# limiter.net
KiCad netlist of a schematic drawn in EAGLE
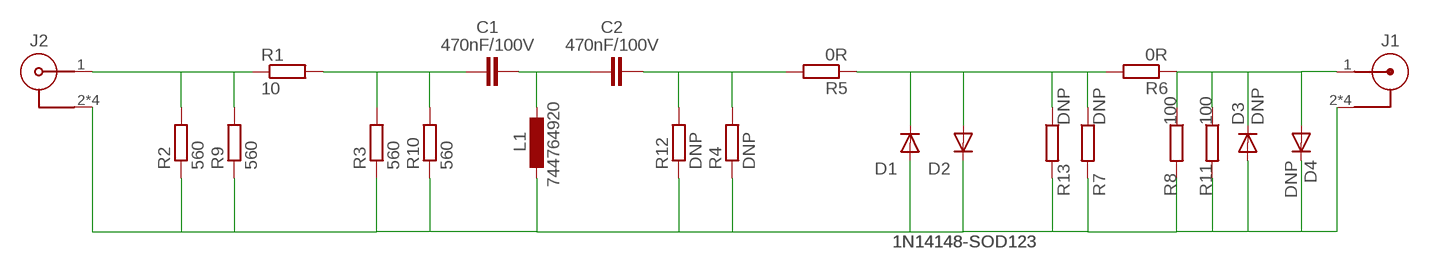
[diagram p0: schematic, sheet 1]

(export (version "E")
  (design (tool "Eeschema 10.0.6"))
  (components
    (comp (ref "C1")
      (value "470nF/100V")
      (footprint "eagle-import:C0805K")
      (libsource (lib "eagle-import") (part "C-EUC0805K"))
    )
    (comp (ref "C2")
      (value "470nF/100V")
      (footprint "eagle-import:C0805K")
      (libsource (lib "eagle-import") (part "C-EUC0805K"))
    )
    (comp (ref "D1")
      (value "1N14148-SOD123")
      (footprint "eagle-import:SOD123")
      (libsource (lib "eagle-import") (part "DIODE-SOD123"))
    )
    (comp (ref "D2")
      (value "1N14148-SOD123")
      (footprint "eagle-import:SOD123")
      (libsource (lib "eagle-import") (part "DIODE-SOD123"))
    )
    (comp (ref "D3")
      (value "DNP")
      (footprint "eagle-import:SOD123")
      (libsource (lib "eagle-import") (part "DIODE-SOD123"))
    )
    (comp (ref "D4")
      (value "DNP")
      (footprint "eagle-import:SOD123")
      (libsource (lib "eagle-import") (part "DIODE-SOD123"))
    )
    (comp (ref "J1")
      (value "60314202124525")
      (footprint "eagle-import:60314202124525")
      (libsource (lib "eagle-import") (part "60314202124525"))
    )
    (comp (ref "J2")
      (value "60312202114509")
      (footprint "eagle-import:60312202114509")
      (libsource (lib "eagle-import") (part "60312202114509"))
    )
    (comp (ref "L1")
      (value "744764920")
      (footprint "eagle-import:L3225M")
      (libsource (lib "eagle-import") (part "L-EUL3225M"))
    )
    (comp (ref "R1")
      (value "10")
      (footprint "eagle-import:R0805")
      (libsource (lib "eagle-import") (part "R-EU_R0805"))
    )
    (comp (ref "R2")
      (value "560")
      (footprint "eagle-import:R0805")
      (libsource (lib "eagle-import") (part "R-EU_R0805"))
    )
    (comp (ref "R3")
      (value "560")
      (footprint "eagle-import:R0805")
      (libsource (lib "eagle-import") (part "R-EU_R0805"))
    )
    (comp (ref "R4")
      (value "DNP")
      (footprint "eagle-import:R0805")
      (libsource (lib "eagle-import") (part "R-EU_R0805"))
    )
    (comp (ref "R5")
      (value "0R")
      (footprint "eagle-import:R0805")
      (libsource (lib "eagle-import") (part "R-EU_R0805"))
    )
    (comp (ref "R6")
      (value "0R")
      (footprint "eagle-import:R0805")
      (libsource (lib "eagle-import") (part "R-EU_R0805"))
    )
    (comp (ref "R7")
      (value "DNP")
      (footprint "eagle-import:R0805")
      (libsource (lib "eagle-import") (part "R-EU_R0805"))
    )
    (comp (ref "R8")
      (value "100")
      (footprint "eagle-import:R0805")
      (libsource (lib "eagle-import") (part "R-EU_R0805"))
    )
    (comp (ref "R9")
      (value "560")
      (footprint "eagle-import:R0805")
      (libsource (lib "eagle-import") (part "R-EU_R0805"))
    )
    (comp (ref "R10")
      (value "560")
      (footprint "eagle-import:R0805")
      (libsource (lib "eagle-import") (part "R-EU_R0805"))
    )
    (comp (ref "R11")
      (value "100")
      (footprint "eagle-import:R0805")
      (libsource (lib "eagle-import") (part "R-EU_R0805"))
    )
    (comp (ref "R12")
      (value "DNP")
      (footprint "eagle-import:R0805")
      (libsource (lib "eagle-import") (part "R-EU_R0805"))
    )
    (comp (ref "R13")
      (value "DNP")
      (footprint "eagle-import:R0805")
      (libsource (lib "eagle-import") (part "R-EU_R0805"))
    )
  )
  (nets
    (net (code "1") (name "Net-(C1-Pad1)") (class "Default")
      (node (ref "C1") (pin "1") (pinfunction "1_1") (pintype "passive"))
      (node (ref "R1") (pin "2") (pinfunction "2_2") (pintype "passive"))
      (node (ref "R10") (pin "2") (pinfunction "2_2") (pintype "passive"))
      (node (ref "R3") (pin "2") (pinfunction "2_2") (pintype "passive"))
    )
    (net (code "2") (name "Net-(C1-Pad2)") (class "Default")
      (node (ref "C1") (pin "2") (pinfunction "2_2") (pintype "passive"))
      (node (ref "C2") (pin "1") (pinfunction "1_1") (pintype "passive"))
      (node (ref "L1") (pin "1") (pinfunction "1_1") (pintype "passive"))
    )
    (net (code "3") (name "Net-(C2-Pad2)") (class "Default")
      (node (ref "C2") (pin "2") (pinfunction "2_2") (pintype "passive"))
      (node (ref "R12") (pin "2") (pinfunction "2_2") (pintype "passive"))
      (node (ref "R4") (pin "2") (pinfunction "2_2") (pintype "passive"))
      (node (ref "R5") (pin "2") (pinfunction "2_2") (pintype "passive"))
    )
    (net (code "4") (name "Net-(D1-PadA)") (class "Default")
      (node (ref "D1") (pin "A") (pinfunction "A_A") (pintype "passive"))
      (node (ref "D2") (pin "C") (pinfunction "C_C") (pintype "passive"))
      (node (ref "D3") (pin "A") (pinfunction "A_A") (pintype "passive"))
      (node (ref "D4") (pin "C") (pinfunction "C_C") (pintype "passive"))
      (node (ref "J1") (pin "2") (pinfunction "2_2") (pintype "passive"))
      (node (ref "J1") (pin "3") (pinfunction "2_3") (pintype "passive"))
      (node (ref "J1") (pin "4") (pinfunction "2_4") (pintype "passive"))
      (node (ref "J1") (pin "5") (pinfunction "2_5") (pintype "passive"))
      (node (ref "J2") (pin "2") (pinfunction "2_2") (pintype "passive"))
      (node (ref "J2") (pin "3") (pinfunction "2_3") (pintype "passive"))
      (node (ref "J2") (pin "4") (pinfunction "2_4") (pintype "passive"))
      (node (ref "J2") (pin "5") (pinfunction "2_5") (pintype "passive"))
      (node (ref "L1") (pin "2") (pinfunction "2_2") (pintype "passive"))
      (node (ref "R10") (pin "1") (pinfunction "1_1") (pintype "passive"))
      (node (ref "R11") (pin "2") (pinfunction "2_2") (pintype "passive"))
      (node (ref "R12") (pin "1") (pinfunction "1_1") (pintype "passive"))
      (node (ref "R13") (pin "2") (pinfunction "2_2") (pintype "passive"))
      (node (ref "R2") (pin "1") (pinfunction "1_1") (pintype "passive"))
      (node (ref "R3") (pin "1") (pinfunction "1_1") (pintype "passive"))
      (node (ref "R4") (pin "1") (pinfunction "1_1") (pintype "passive"))
      (node (ref "R7") (pin "2") (pinfunction "2_2") (pintype "passive"))
      (node (ref "R8") (pin "2") (pinfunction "2_2") (pintype "passive"))
      (node (ref "R9") (pin "1") (pinfunction "1_1") (pintype "passive"))
    )
    (net (code "5") (name "Net-(D1-PadC)") (class "Default")
      (node (ref "D1") (pin "C") (pinfunction "C_C") (pintype "passive"))
      (node (ref "D2") (pin "A") (pinfunction "A_A") (pintype "passive"))
      (node (ref "R13") (pin "1") (pinfunction "1_1") (pintype "passive"))
      (node (ref "R5") (pin "1") (pinfunction "1_1") (pintype "passive"))
      (node (ref "R6") (pin "2") (pinfunction "2_2") (pintype "passive"))
      (node (ref "R7") (pin "1") (pinfunction "1_1") (pintype "passive"))
    )
    (net (code "6") (name "Net-(D3-PadC)") (class "Default")
      (node (ref "D3") (pin "C") (pinfunction "C_C") (pintype "passive"))
      (node (ref "D4") (pin "A") (pinfunction "A_A") (pintype "passive"))
      (node (ref "J1") (pin "1") (pinfunction "1_1") (pintype "passive"))
      (node (ref "R11") (pin "1") (pinfunction "1_1") (pintype "passive"))
      (node (ref "R6") (pin "1") (pinfunction "1_1") (pintype "passive"))
      (node (ref "R8") (pin "1") (pinfunction "1_1") (pintype "passive"))
    )
    (net (code "7") (name "Net-(J2-Pad1)") (class "Default")
      (node (ref "J2") (pin "1") (pinfunction "1_1") (pintype "passive"))
      (node (ref "R1") (pin "1") (pinfunction "1_1") (pintype "passive"))
      (node (ref "R2") (pin "2") (pinfunction "2_2") (pintype "passive"))
      (node (ref "R9") (pin "2") (pinfunction "2_2") (pintype "passive"))
    )
  )
)
